# PULSECAPS.net
KiCad netlist of a schematic drawn in Altium Designer
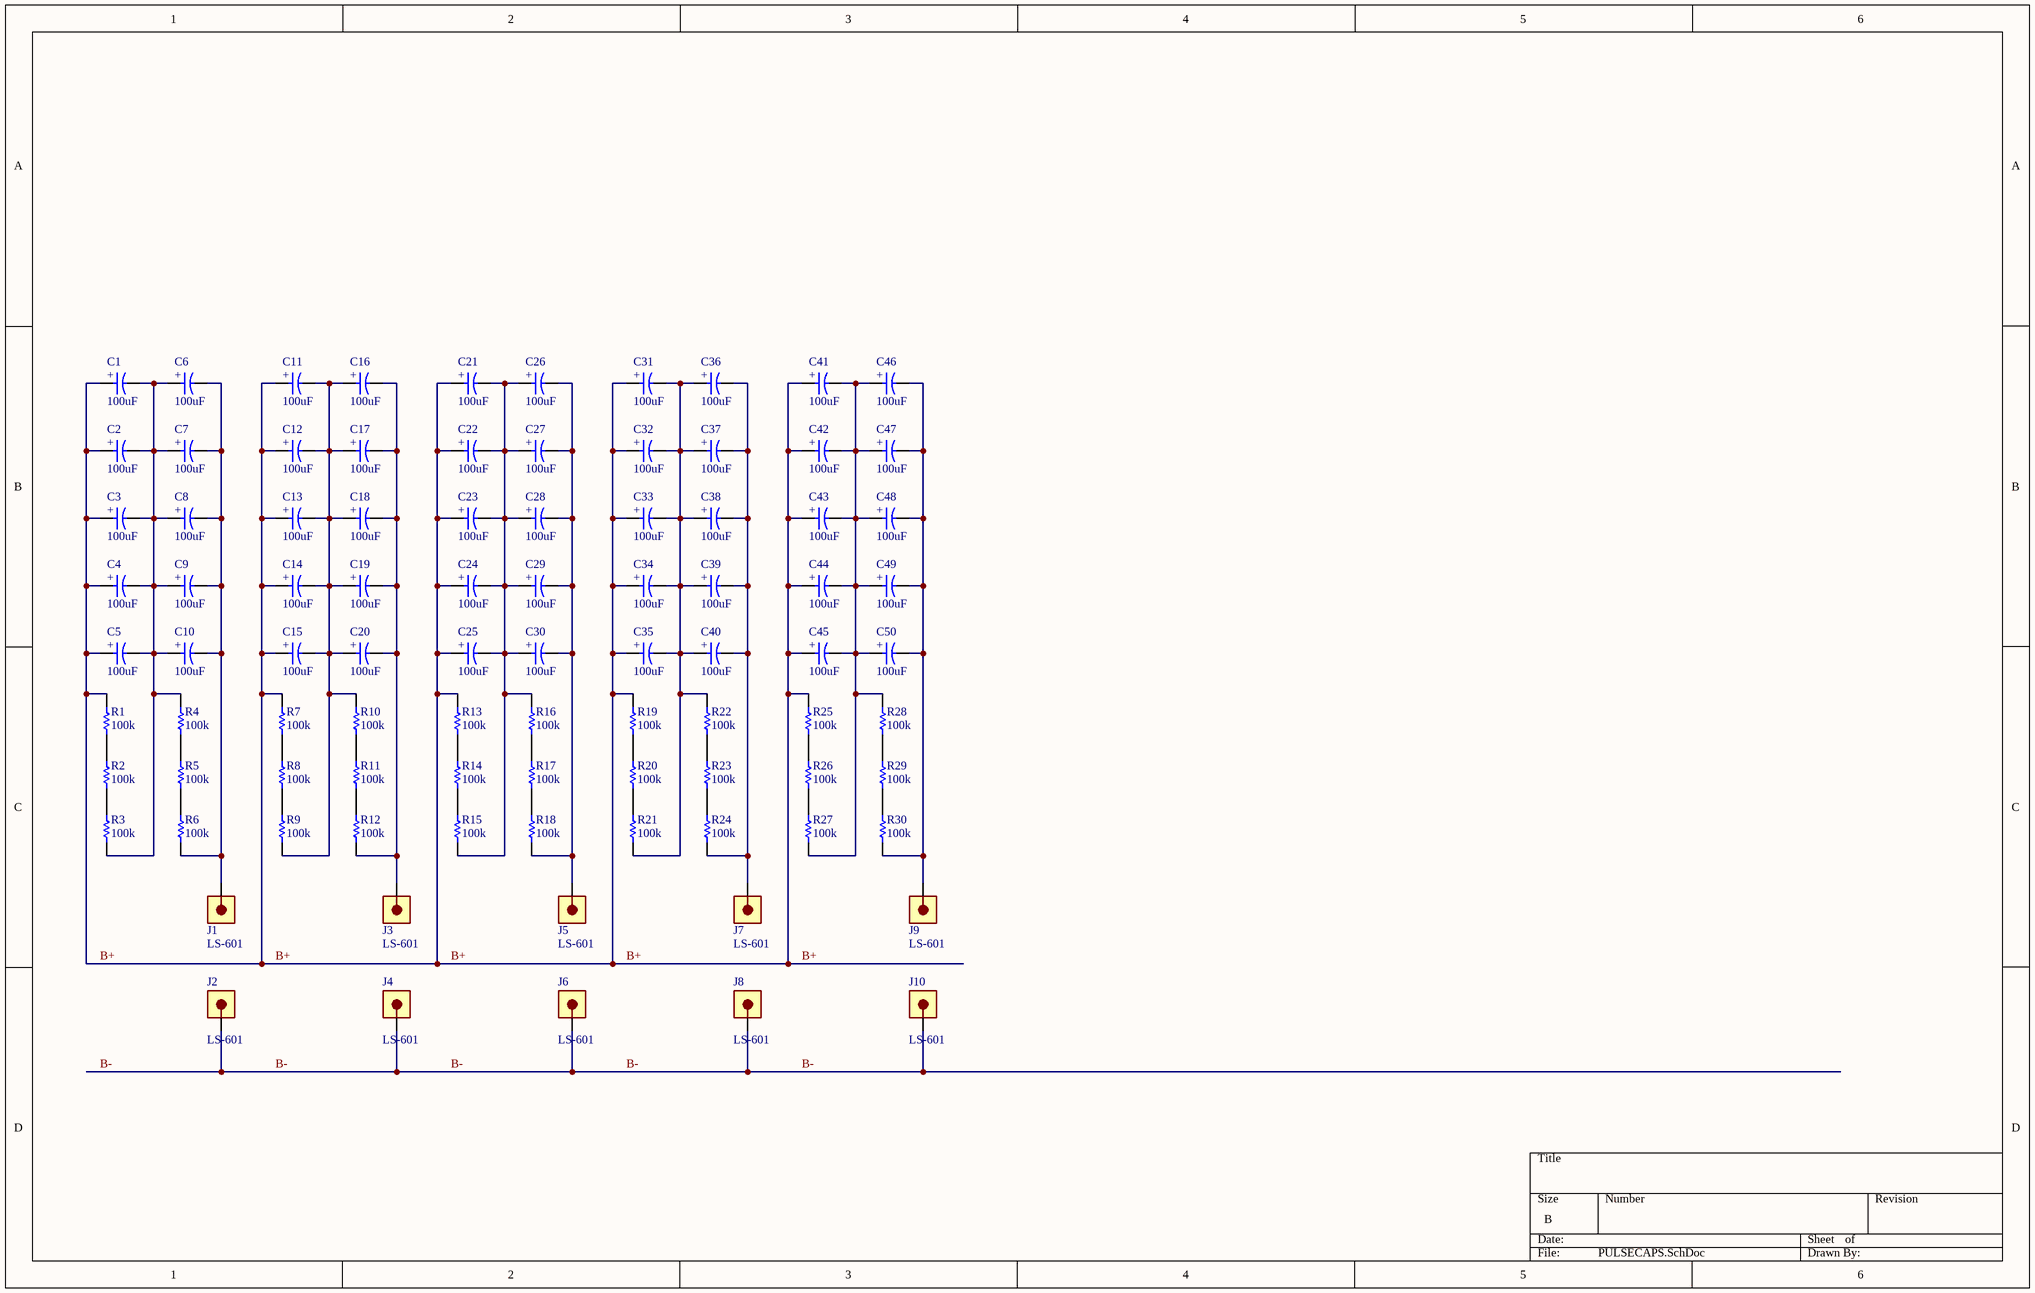
[diagram p0: PULSECAPS.SchDoc]

(export (version "E")
  (design (tool "Eeschema 10.0.6"))
  (components
    (comp (ref "C1")
      (value "100uF")
      (footprint "C_CAN_TH_7.5MM_LEADS")
      (description "C - CAPACITOR - ELECTROLYTIC - 100uF - 400V")
      (fields (field (name "LCSC PART #") "C441621") (field (name "Comment") "400BXW100MEFR16X30"))
      (libsource (lib "JLC_PCB") (part "400BXW100MEFR16X30"))
    )
    (comp (ref "C2")
      (value "100uF")
      (footprint "C_CAN_TH_7.5MM_LEADS")
      (description "C - CAPACITOR - ELECTROLYTIC - 100uF - 400V")
      (fields (field (name "LCSC PART #") "C441621") (field (name "Comment") "400BXW100MEFR16X30"))
      (libsource (lib "JLC_PCB") (part "400BXW100MEFR16X30"))
    )
    (comp (ref "C3")
      (value "100uF")
      (footprint "C_CAN_TH_7.5MM_LEADS")
      (description "C - CAPACITOR - ELECTROLYTIC - 100uF - 400V")
      (fields (field (name "LCSC PART #") "C441621") (field (name "Comment") "400BXW100MEFR16X30"))
      (libsource (lib "JLC_PCB") (part "400BXW100MEFR16X30"))
    )
    (comp (ref "C4")
      (value "100uF")
      (footprint "C_CAN_TH_7.5MM_LEADS")
      (description "C - CAPACITOR - ELECTROLYTIC - 100uF - 400V")
      (fields (field (name "LCSC PART #") "C441621") (field (name "Comment") "400BXW100MEFR16X30"))
      (libsource (lib "JLC_PCB") (part "400BXW100MEFR16X30"))
    )
    (comp (ref "C5")
      (value "100uF")
      (footprint "C_CAN_TH_7.5MM_LEADS")
      (description "C - CAPACITOR - ELECTROLYTIC - 100uF - 400V")
      (fields (field (name "LCSC PART #") "C441621") (field (name "Comment") "400BXW100MEFR16X30"))
      (libsource (lib "JLC_PCB") (part "400BXW100MEFR16X30"))
    )
    (comp (ref "C6")
      (value "100uF")
      (footprint "C_CAN_TH_7.5MM_LEADS")
      (description "C - CAPACITOR - ELECTROLYTIC - 100uF - 400V")
      (fields (field (name "LCSC PART #") "C441621") (field (name "Comment") "400BXW100MEFR16X30"))
      (libsource (lib "JLC_PCB") (part "400BXW100MEFR16X30"))
    )
    (comp (ref "C7")
      (value "100uF")
      (footprint "C_CAN_TH_7.5MM_LEADS")
      (description "C - CAPACITOR - ELECTROLYTIC - 100uF - 400V")
      (fields (field (name "LCSC PART #") "C441621") (field (name "Comment") "400BXW100MEFR16X30"))
      (libsource (lib "JLC_PCB") (part "400BXW100MEFR16X30"))
    )
    (comp (ref "C8")
      (value "100uF")
      (footprint "C_CAN_TH_7.5MM_LEADS")
      (description "C - CAPACITOR - ELECTROLYTIC - 100uF - 400V")
      (fields (field (name "LCSC PART #") "C441621") (field (name "Comment") "400BXW100MEFR16X30"))
      (libsource (lib "JLC_PCB") (part "400BXW100MEFR16X30"))
    )
    (comp (ref "C9")
      (value "100uF")
      (footprint "C_CAN_TH_7.5MM_LEADS")
      (description "C - CAPACITOR - ELECTROLYTIC - 100uF - 400V")
      (fields (field (name "LCSC PART #") "C441621") (field (name "Comment") "400BXW100MEFR16X30"))
      (libsource (lib "JLC_PCB") (part "400BXW100MEFR16X30"))
    )
    (comp (ref "C10")
      (value "100uF")
      (footprint "C_CAN_TH_7.5MM_LEADS")
      (description "C - CAPACITOR - ELECTROLYTIC - 100uF - 400V")
      (fields (field (name "LCSC PART #") "C441621") (field (name "Comment") "400BXW100MEFR16X30"))
      (libsource (lib "JLC_PCB") (part "400BXW100MEFR16X30"))
    )
    (comp (ref "C11")
      (value "100uF")
      (footprint "C_CAN_TH_7.5MM_LEADS")
      (description "C - CAPACITOR - ELECTROLYTIC - 100uF - 400V")
      (fields (field (name "LCSC PART #") "C441621") (field (name "Comment") "400BXW100MEFR16X30"))
      (libsource (lib "JLC_PCB") (part "400BXW100MEFR16X30"))
    )
    (comp (ref "C12")
      (value "100uF")
      (footprint "C_CAN_TH_7.5MM_LEADS")
      (description "C - CAPACITOR - ELECTROLYTIC - 100uF - 400V")
      (fields (field (name "LCSC PART #") "C441621") (field (name "Comment") "400BXW100MEFR16X30"))
      (libsource (lib "JLC_PCB") (part "400BXW100MEFR16X30"))
    )
    (comp (ref "C13")
      (value "100uF")
      (footprint "C_CAN_TH_7.5MM_LEADS")
      (description "C - CAPACITOR - ELECTROLYTIC - 100uF - 400V")
      (fields (field (name "LCSC PART #") "C441621") (field (name "Comment") "400BXW100MEFR16X30"))
      (libsource (lib "JLC_PCB") (part "400BXW100MEFR16X30"))
    )
    (comp (ref "C14")
      (value "100uF")
      (footprint "C_CAN_TH_7.5MM_LEADS")
      (description "C - CAPACITOR - ELECTROLYTIC - 100uF - 400V")
      (fields (field (name "LCSC PART #") "C441621") (field (name "Comment") "400BXW100MEFR16X30"))
      (libsource (lib "JLC_PCB") (part "400BXW100MEFR16X30"))
    )
    (comp (ref "C15")
      (value "100uF")
      (footprint "C_CAN_TH_7.5MM_LEADS")
      (description "C - CAPACITOR - ELECTROLYTIC - 100uF - 400V")
      (fields (field (name "LCSC PART #") "C441621") (field (name "Comment") "400BXW100MEFR16X30"))
      (libsource (lib "JLC_PCB") (part "400BXW100MEFR16X30"))
    )
    (comp (ref "C16")
      (value "100uF")
      (footprint "C_CAN_TH_7.5MM_LEADS")
      (description "C - CAPACITOR - ELECTROLYTIC - 100uF - 400V")
      (fields (field (name "LCSC PART #") "C441621") (field (name "Comment") "400BXW100MEFR16X30"))
      (libsource (lib "JLC_PCB") (part "400BXW100MEFR16X30"))
    )
    (comp (ref "C17")
      (value "100uF")
      (footprint "C_CAN_TH_7.5MM_LEADS")
      (description "C - CAPACITOR - ELECTROLYTIC - 100uF - 400V")
      (fields (field (name "LCSC PART #") "C441621") (field (name "Comment") "400BXW100MEFR16X30"))
      (libsource (lib "JLC_PCB") (part "400BXW100MEFR16X30"))
    )
    (comp (ref "C18")
      (value "100uF")
      (footprint "C_CAN_TH_7.5MM_LEADS")
      (description "C - CAPACITOR - ELECTROLYTIC - 100uF - 400V")
      (fields (field (name "LCSC PART #") "C441621") (field (name "Comment") "400BXW100MEFR16X30"))
      (libsource (lib "JLC_PCB") (part "400BXW100MEFR16X30"))
    )
    (comp (ref "C19")
      (value "100uF")
      (footprint "C_CAN_TH_7.5MM_LEADS")
      (description "C - CAPACITOR - ELECTROLYTIC - 100uF - 400V")
      (fields (field (name "LCSC PART #") "C441621") (field (name "Comment") "400BXW100MEFR16X30"))
      (libsource (lib "JLC_PCB") (part "400BXW100MEFR16X30"))
    )
    (comp (ref "C20")
      (value "100uF")
      (footprint "C_CAN_TH_7.5MM_LEADS")
      (description "C - CAPACITOR - ELECTROLYTIC - 100uF - 400V")
      (fields (field (name "LCSC PART #") "C441621") (field (name "Comment") "400BXW100MEFR16X30"))
      (libsource (lib "JLC_PCB") (part "400BXW100MEFR16X30"))
    )
    (comp (ref "C21")
      (value "100uF")
      (footprint "C_CAN_TH_7.5MM_LEADS")
      (description "C - CAPACITOR - ELECTROLYTIC - 100uF - 400V")
      (fields (field (name "LCSC PART #") "C441621") (field (name "Comment") "400BXW100MEFR16X30"))
      (libsource (lib "JLC_PCB") (part "400BXW100MEFR16X30"))
    )
    (comp (ref "C22")
      (value "100uF")
      (footprint "C_CAN_TH_7.5MM_LEADS")
      (description "C - CAPACITOR - ELECTROLYTIC - 100uF - 400V")
      (fields (field (name "LCSC PART #") "C441621") (field (name "Comment") "400BXW100MEFR16X30"))
      (libsource (lib "JLC_PCB") (part "400BXW100MEFR16X30"))
    )
    (comp (ref "C23")
      (value "100uF")
      (footprint "C_CAN_TH_7.5MM_LEADS")
      (description "C - CAPACITOR - ELECTROLYTIC - 100uF - 400V")
      (fields (field (name "LCSC PART #") "C441621") (field (name "Comment") "400BXW100MEFR16X30"))
      (libsource (lib "JLC_PCB") (part "400BXW100MEFR16X30"))
    )
    (comp (ref "C24")
      (value "100uF")
      (footprint "C_CAN_TH_7.5MM_LEADS")
      (description "C - CAPACITOR - ELECTROLYTIC - 100uF - 400V")
      (fields (field (name "LCSC PART #") "C441621") (field (name "Comment") "400BXW100MEFR16X30"))
      (libsource (lib "JLC_PCB") (part "400BXW100MEFR16X30"))
    )
    (comp (ref "C25")
      (value "100uF")
      (footprint "C_CAN_TH_7.5MM_LEADS")
      (description "C - CAPACITOR - ELECTROLYTIC - 100uF - 400V")
      (fields (field (name "LCSC PART #") "C441621") (field (name "Comment") "400BXW100MEFR16X30"))
      (libsource (lib "JLC_PCB") (part "400BXW100MEFR16X30"))
    )
    (comp (ref "C26")
      (value "100uF")
      (footprint "C_CAN_TH_7.5MM_LEADS")
      (description "C - CAPACITOR - ELECTROLYTIC - 100uF - 400V")
      (fields (field (name "LCSC PART #") "C441621") (field (name "Comment") "400BXW100MEFR16X30"))
      (libsource (lib "JLC_PCB") (part "400BXW100MEFR16X30"))
    )
    (comp (ref "C27")
      (value "100uF")
      (footprint "C_CAN_TH_7.5MM_LEADS")
      (description "C - CAPACITOR - ELECTROLYTIC - 100uF - 400V")
      (fields (field (name "LCSC PART #") "C441621") (field (name "Comment") "400BXW100MEFR16X30"))
      (libsource (lib "JLC_PCB") (part "400BXW100MEFR16X30"))
    )
    (comp (ref "C28")
      (value "100uF")
      (footprint "C_CAN_TH_7.5MM_LEADS")
      (description "C - CAPACITOR - ELECTROLYTIC - 100uF - 400V")
      (fields (field (name "LCSC PART #") "C441621") (field (name "Comment") "400BXW100MEFR16X30"))
      (libsource (lib "JLC_PCB") (part "400BXW100MEFR16X30"))
    )
    (comp (ref "C29")
      (value "100uF")
      (footprint "C_CAN_TH_7.5MM_LEADS")
      (description "C - CAPACITOR - ELECTROLYTIC - 100uF - 400V")
      (fields (field (name "LCSC PART #") "C441621") (field (name "Comment") "400BXW100MEFR16X30"))
      (libsource (lib "JLC_PCB") (part "400BXW100MEFR16X30"))
    )
    (comp (ref "C30")
      (value "100uF")
      (footprint "C_CAN_TH_7.5MM_LEADS")
      (description "C - CAPACITOR - ELECTROLYTIC - 100uF - 400V")
      (fields (field (name "LCSC PART #") "C441621") (field (name "Comment") "400BXW100MEFR16X30"))
      (libsource (lib "JLC_PCB") (part "400BXW100MEFR16X30"))
    )
    (comp (ref "C31")
      (value "100uF")
      (footprint "C_CAN_TH_7.5MM_LEADS")
      (description "C - CAPACITOR - ELECTROLYTIC - 100uF - 400V")
      (fields (field (name "LCSC PART #") "C441621") (field (name "Comment") "400BXW100MEFR16X30"))
      (libsource (lib "JLC_PCB") (part "400BXW100MEFR16X30"))
    )
    (comp (ref "C32")
      (value "100uF")
      (footprint "C_CAN_TH_7.5MM_LEADS")
      (description "C - CAPACITOR - ELECTROLYTIC - 100uF - 400V")
      (fields (field (name "LCSC PART #") "C441621") (field (name "Comment") "400BXW100MEFR16X30"))
      (libsource (lib "JLC_PCB") (part "400BXW100MEFR16X30"))
    )
    (comp (ref "C33")
      (value "100uF")
      (footprint "C_CAN_TH_7.5MM_LEADS")
      (description "C - CAPACITOR - ELECTROLYTIC - 100uF - 400V")
      (fields (field (name "LCSC PART #") "C441621") (field (name "Comment") "400BXW100MEFR16X30"))
      (libsource (lib "JLC_PCB") (part "400BXW100MEFR16X30"))
    )
    (comp (ref "C34")
      (value "100uF")
      (footprint "C_CAN_TH_7.5MM_LEADS")
      (description "C - CAPACITOR - ELECTROLYTIC - 100uF - 400V")
      (fields (field (name "LCSC PART #") "C441621") (field (name "Comment") "400BXW100MEFR16X30"))
      (libsource (lib "JLC_PCB") (part "400BXW100MEFR16X30"))
    )
    (comp (ref "C35")
      (value "100uF")
      (footprint "C_CAN_TH_7.5MM_LEADS")
      (description "C - CAPACITOR - ELECTROLYTIC - 100uF - 400V")
      (fields (field (name "LCSC PART #") "C441621") (field (name "Comment") "400BXW100MEFR16X30"))
      (libsource (lib "JLC_PCB") (part "400BXW100MEFR16X30"))
    )
    (comp (ref "C36")
      (value "100uF")
      (footprint "C_CAN_TH_7.5MM_LEADS")
      (description "C - CAPACITOR - ELECTROLYTIC - 100uF - 400V")
      (fields (field (name "LCSC PART #") "C441621") (field (name "Comment") "400BXW100MEFR16X30"))
      (libsource (lib "JLC_PCB") (part "400BXW100MEFR16X30"))
    )
    (comp (ref "C37")
      (value "100uF")
      (footprint "C_CAN_TH_7.5MM_LEADS")
      (description "C - CAPACITOR - ELECTROLYTIC - 100uF - 400V")
      (fields (field (name "LCSC PART #") "C441621") (field (name "Comment") "400BXW100MEFR16X30"))
      (libsource (lib "JLC_PCB") (part "400BXW100MEFR16X30"))
    )
    (comp (ref "C38")
      (value "100uF")
      (footprint "C_CAN_TH_7.5MM_LEADS")
      (description "C - CAPACITOR - ELECTROLYTIC - 100uF - 400V")
      (fields (field (name "LCSC PART #") "C441621") (field (name "Comment") "400BXW100MEFR16X30"))
      (libsource (lib "JLC_PCB") (part "400BXW100MEFR16X30"))
    )
    (comp (ref "C39")
      (value "100uF")
      (footprint "C_CAN_TH_7.5MM_LEADS")
      (description "C - CAPACITOR - ELECTROLYTIC - 100uF - 400V")
      (fields (field (name "LCSC PART #") "C441621") (field (name "Comment") "400BXW100MEFR16X30"))
      (libsource (lib "JLC_PCB") (part "400BXW100MEFR16X30"))
    )
    (comp (ref "C40")
      (value "100uF")
      (footprint "C_CAN_TH_7.5MM_LEADS")
      (description "C - CAPACITOR - ELECTROLYTIC - 100uF - 400V")
      (fields (field (name "LCSC PART #") "C441621") (field (name "Comment") "400BXW100MEFR16X30"))
      (libsource (lib "JLC_PCB") (part "400BXW100MEFR16X30"))
    )
    (comp (ref "C41")
      (value "100uF")
      (footprint "C_CAN_TH_7.5MM_LEADS")
      (description "C - CAPACITOR - ELECTROLYTIC - 100uF - 400V")
      (fields (field (name "LCSC PART #") "C441621") (field (name "Comment") "400BXW100MEFR16X30"))
      (libsource (lib "JLC_PCB") (part "400BXW100MEFR16X30"))
    )
    (comp (ref "C42")
      (value "100uF")
      (footprint "C_CAN_TH_7.5MM_LEADS")
      (description "C - CAPACITOR - ELECTROLYTIC - 100uF - 400V")
      (fields (field (name "LCSC PART #") "C441621") (field (name "Comment") "400BXW100MEFR16X30"))
      (libsource (lib "JLC_PCB") (part "400BXW100MEFR16X30"))
    )
    (comp (ref "C43")
      (value "100uF")
      (footprint "C_CAN_TH_7.5MM_LEADS")
      (description "C - CAPACITOR - ELECTROLYTIC - 100uF - 400V")
      (fields (field (name "LCSC PART #") "C441621") (field (name "Comment") "400BXW100MEFR16X30"))
      (libsource (lib "JLC_PCB") (part "400BXW100MEFR16X30"))
    )
    (comp (ref "C44")
      (value "100uF")
      (footprint "C_CAN_TH_7.5MM_LEADS")
      (description "C - CAPACITOR - ELECTROLYTIC - 100uF - 400V")
      (fields (field (name "LCSC PART #") "C441621") (field (name "Comment") "400BXW100MEFR16X30"))
      (libsource (lib "JLC_PCB") (part "400BXW100MEFR16X30"))
    )
    (comp (ref "C45")
      (value "100uF")
      (footprint "C_CAN_TH_7.5MM_LEADS")
      (description "C - CAPACITOR - ELECTROLYTIC - 100uF - 400V")
      (fields (field (name "LCSC PART #") "C441621") (field (name "Comment") "400BXW100MEFR16X30"))
      (libsource (lib "JLC_PCB") (part "400BXW100MEFR16X30"))
    )
    (comp (ref "C46")
      (value "100uF")
      (footprint "C_CAN_TH_7.5MM_LEADS")
      (description "C - CAPACITOR - ELECTROLYTIC - 100uF - 400V")
      (fields (field (name "LCSC PART #") "C441621") (field (name "Comment") "400BXW100MEFR16X30"))
      (libsource (lib "JLC_PCB") (part "400BXW100MEFR16X30"))
    )
    (comp (ref "C47")
      (value "100uF")
      (footprint "C_CAN_TH_7.5MM_LEADS")
      (description "C - CAPACITOR - ELECTROLYTIC - 100uF - 400V")
      (fields (field (name "LCSC PART #") "C441621") (field (name "Comment") "400BXW100MEFR16X30"))
      (libsource (lib "JLC_PCB") (part "400BXW100MEFR16X30"))
    )
    (comp (ref "C48")
      (value "100uF")
      (footprint "C_CAN_TH_7.5MM_LEADS")
      (description "C - CAPACITOR - ELECTROLYTIC - 100uF - 400V")
      (fields (field (name "LCSC PART #") "C441621") (field (name "Comment") "400BXW100MEFR16X30"))
      (libsource (lib "JLC_PCB") (part "400BXW100MEFR16X30"))
    )
    (comp (ref "C49")
      (value "100uF")
      (footprint "C_CAN_TH_7.5MM_LEADS")
      (description "C - CAPACITOR - ELECTROLYTIC - 100uF - 400V")
      (fields (field (name "LCSC PART #") "C441621") (field (name "Comment") "400BXW100MEFR16X30"))
      (libsource (lib "JLC_PCB") (part "400BXW100MEFR16X30"))
    )
    (comp (ref "C50")
      (value "100uF")
      (footprint "C_CAN_TH_7.5MM_LEADS")
      (description "C - CAPACITOR - ELECTROLYTIC - 100uF - 400V")
      (fields (field (name "LCSC PART #") "C441621") (field (name "Comment") "400BXW100MEFR16X30"))
      (libsource (lib "JLC_PCB") (part "400BXW100MEFR16X30"))
    )
    (comp (ref "J1")
      (value "LS-601")
      (footprint "LS-601")
      (description "J - JACK - FUSEHOLDER - 6X30 - THT")
      (fields (field (name "LCSC PART #") "C182321"))
      (libsource (lib "JLC_PCB") (part "LS-601"))
    )
    (comp (ref "J2")
      (value "LS-601")
      (footprint "LS-601")
      (description "J - JACK - FUSEHOLDER - 6X30 - THT")
      (fields (field (name "LCSC PART #") "C182321"))
      (libsource (lib "") (part "LS-601_1"))
    )
    (comp (ref "J3")
      (value "LS-601")
      (footprint "LS-601")
      (description "J - JACK - FUSEHOLDER - 6X30 - THT")
      (fields (field (name "LCSC PART #") "C182321"))
      (libsource (lib "JLC_PCB") (part "LS-601"))
    )
    (comp (ref "J4")
      (value "LS-601")
      (footprint "LS-601")
      (description "J - JACK - FUSEHOLDER - 6X30 - THT")
      (fields (field (name "LCSC PART #") "C182321"))
      (libsource (lib "") (part "LS-601_1"))
    )
    (comp (ref "J5")
      (value "LS-601")
      (footprint "LS-601")
      (description "J - JACK - FUSEHOLDER - 6X30 - THT")
      (fields (field (name "LCSC PART #") "C182321"))
      (libsource (lib "JLC_PCB") (part "LS-601"))
    )
    (comp (ref "J6")
      (value "LS-601")
      (footprint "LS-601")
      (description "J - JACK - FUSEHOLDER - 6X30 - THT")
      (fields (field (name "LCSC PART #") "C182321"))
      (libsource (lib "") (part "LS-601_1"))
    )
    (comp (ref "J7")
      (value "LS-601")
      (footprint "LS-601")
      (description "J - JACK - FUSEHOLDER - 6X30 - THT")
      (fields (field (name "LCSC PART #") "C182321"))
      (libsource (lib "JLC_PCB") (part "LS-601"))
    )
    (comp (ref "J8")
      (value "LS-601")
      (footprint "LS-601")
      (description "J - JACK - FUSEHOLDER - 6X30 - THT")
      (fields (field (name "LCSC PART #") "C182321"))
      (libsource (lib "") (part "LS-601_1"))
    )
    (comp (ref "J9")
      (value "LS-601")
      (footprint "LS-601")
      (description "J - JACK - FUSEHOLDER - 6X30 - THT")
      (fields (field (name "LCSC PART #") "C182321"))
      (libsource (lib "JLC_PCB") (part "LS-601"))
    )
    (comp (ref "J10")
      (value "LS-601")
      (footprint "LS-601")
      (description "J - JACK - FUSEHOLDER - 6X30 - THT")
      (fields (field (name "LCSC PART #") "C182321"))
      (libsource (lib "") (part "LS-601_1"))
    )
    (comp (ref "R1")
      (value "100k")
      (footprint "R_1206")
      (description "R - RESISTOR - SMD - 100k - 1% - 1206")
      (fields (field (name "LCSC PART #") "C17900") (field (name "Comment") "1206W4F1003T5E"))
      (libsource (lib "JLC_PCB") (part "1206W4F1003T5E"))
    )
    (comp (ref "R2")
      (value "100k")
      (footprint "R_1206")
      (description "R - RESISTOR - SMD - 100k - 1% - 1206")
      (fields (field (name "LCSC PART #") "C17900") (field (name "Comment") "1206W4F1003T5E"))
      (libsource (lib "JLC_PCB") (part "1206W4F1003T5E"))
    )
    (comp (ref "R3")
      (value "100k")
      (footprint "R_1206")
      (description "R - RESISTOR - SMD - 100k - 1% - 1206")
      (fields (field (name "LCSC PART #") "C17900") (field (name "Comment") "1206W4F1003T5E"))
      (libsource (lib "JLC_PCB") (part "1206W4F1003T5E"))
    )
    (comp (ref "R4")
      (value "100k")
      (footprint "R_1206")
      (description "R - RESISTOR - SMD - 100k - 1% - 1206")
      (fields (field (name "LCSC PART #") "C17900") (field (name "Comment") "1206W4F1003T5E"))
      (libsource (lib "JLC_PCB") (part "1206W4F1003T5E"))
    )
    (comp (ref "R5")
      (value "100k")
      (footprint "R_1206")
      (description "R - RESISTOR - SMD - 100k - 1% - 1206")
      (fields (field (name "LCSC PART #") "C17900") (field (name "Comment") "1206W4F1003T5E"))
      (libsource (lib "JLC_PCB") (part "1206W4F1003T5E"))
    )
    (comp (ref "R6")
      (value "100k")
      (footprint "R_1206")
      (description "R - RESISTOR - SMD - 100k - 1% - 1206")
      (fields (field (name "LCSC PART #") "C17900") (field (name "Comment") "1206W4F1003T5E"))
      (libsource (lib "JLC_PCB") (part "1206W4F1003T5E"))
    )
    (comp (ref "R7")
      (value "100k")
      (footprint "R_1206")
      (description "R - RESISTOR - SMD - 100k - 1% - 1206")
      (fields (field (name "LCSC PART #") "C17900") (field (name "Comment") "1206W4F1003T5E"))
      (libsource (lib "JLC_PCB") (part "1206W4F1003T5E"))
    )
    (comp (ref "R8")
      (value "100k")
      (footprint "R_1206")
      (description "R - RESISTOR - SMD - 100k - 1% - 1206")
      (fields (field (name "LCSC PART #") "C17900") (field (name "Comment") "1206W4F1003T5E"))
      (libsource (lib "JLC_PCB") (part "1206W4F1003T5E"))
    )
    (comp (ref "R9")
      (value "100k")
      (footprint "R_1206")
      (description "R - RESISTOR - SMD - 100k - 1% - 1206")
      (fields (field (name "LCSC PART #") "C17900") (field (name "Comment") "1206W4F1003T5E"))
      (libsource (lib "JLC_PCB") (part "1206W4F1003T5E"))
    )
    (comp (ref "R10")
      (value "100k")
      (footprint "R_1206")
      (description "R - RESISTOR - SMD - 100k - 1% - 1206")
      (fields (field (name "LCSC PART #") "C17900") (field (name "Comment") "1206W4F1003T5E"))
      (libsource (lib "JLC_PCB") (part "1206W4F1003T5E"))
    )
    (comp (ref "R11")
      (value "100k")
      (footprint "R_1206")
      (description "R - RESISTOR - SMD - 100k - 1% - 1206")
      (fields (field (name "LCSC PART #") "C17900") (field (name "Comment") "1206W4F1003T5E"))
      (libsource (lib "JLC_PCB") (part "1206W4F1003T5E"))
    )
    (comp (ref "R12")
      (value "100k")
      (footprint "R_1206")
      (description "R - RESISTOR - SMD - 100k - 1% - 1206")
      (fields (field (name "LCSC PART #") "C17900") (field (name "Comment") "1206W4F1003T5E"))
      (libsource (lib "JLC_PCB") (part "1206W4F1003T5E"))
    )
    (comp (ref "R13")
      (value "100k")
      (footprint "R_1206")
      (description "R - RESISTOR - SMD - 100k - 1% - 1206")
      (fields (field (name "LCSC PART #") "C17900") (field (name "Comment") "1206W4F1003T5E"))
      (libsource (lib "JLC_PCB") (part "1206W4F1003T5E"))
    )
    (comp (ref "R14")
      (value "100k")
      (footprint "R_1206")
      (description "R - RESISTOR - SMD - 100k - 1% - 1206")
      (fields (field (name "LCSC PART #") "C17900") (field (name "Comment") "1206W4F1003T5E"))
      (libsource (lib "JLC_PCB") (part "1206W4F1003T5E"))
    )
    (comp (ref "R15")
      (value "100k")
      (footprint "R_1206")
      (description "R - RESISTOR - SMD - 100k - 1% - 1206")
      (fields (field (name "LCSC PART #") "C17900") (field (name "Comment") "1206W4F1003T5E"))
      (libsource (lib "JLC_PCB") (part "1206W4F1003T5E"))
    )
    (comp (ref "R16")
      (value "100k")
      (footprint "R_1206")
      (description "R - RESISTOR - SMD - 100k - 1% - 1206")
      (fields (field (name "LCSC PART #") "C17900") (field (name "Comment") "1206W4F1003T5E"))
      (libsource (lib "JLC_PCB") (part "1206W4F1003T5E"))
    )
    (comp (ref "R17")
      (value "100k")
      (footprint "R_1206")
      (description "R - RESISTOR - SMD - 100k - 1% - 1206")
      (fields (field (name "LCSC PART #") "C17900") (field (name "Comment") "1206W4F1003T5E"))
      (libsource (lib "JLC_PCB") (part "1206W4F1003T5E"))
    )
    (comp (ref "R18")
      (value "100k")
      (footprint "R_1206")
      (description "R - RESISTOR - SMD - 100k - 1% - 1206")
      (fields (field (name "LCSC PART #") "C17900") (field (name "Comment") "1206W4F1003T5E"))
      (libsource (lib "JLC_PCB") (part "1206W4F1003T5E"))
    )
    (comp (ref "R19")
      (value "100k")
      (footprint "R_1206")
      (description "R - RESISTOR - SMD - 100k - 1% - 1206")
      (fields (field (name "LCSC PART #") "C17900") (field (name "Comment") "1206W4F1003T5E"))
      (libsource (lib "JLC_PCB") (part "1206W4F1003T5E"))
    )
    (comp (ref "R20")
      (value "100k")
      (footprint "R_1206")
      (description "R - RESISTOR - SMD - 100k - 1% - 1206")
      (fields (field (name "LCSC PART #") "C17900") (field (name "Comment") "1206W4F1003T5E"))
      (libsource (lib "JLC_PCB") (part "1206W4F1003T5E"))
    )
    (comp (ref "R21")
      (value "100k")
      (footprint "R_1206")
      (description "R - RESISTOR - SMD - 100k - 1% - 1206")
      (fields (field (name "LCSC PART #") "C17900") (field (name "Comment") "1206W4F1003T5E"))
      (libsource (lib "JLC_PCB") (part "1206W4F1003T5E"))
    )
    (comp (ref "R22")
      (value "100k")
      (footprint "R_1206")
      (description "R - RESISTOR - SMD - 100k - 1% - 1206")
      (fields (field (name "LCSC PART #") "C17900") (field (name "Comment") "1206W4F1003T5E"))
      (libsource (lib "JLC_PCB") (part "1206W4F1003T5E"))
    )
    (comp (ref "R23")
      (value "100k")
      (footprint "R_1206")
      (description "R - RESISTOR - SMD - 100k - 1% - 1206")
      (fields (field (name "LCSC PART #") "C17900") (field (name "Comment") "1206W4F1003T5E"))
      (libsource (lib "JLC_PCB") (part "1206W4F1003T5E"))
    )
    (comp (ref "R24")
      (value "100k")
      (footprint "R_1206")
      (description "R - RESISTOR - SMD - 100k - 1% - 1206")
      (fields (field (name "LCSC PART #") "C17900") (field (name "Comment") "1206W4F1003T5E"))
      (libsource (lib "JLC_PCB") (part "1206W4F1003T5E"))
    )
    (comp (ref "R25")
      (value "100k")
      (footprint "R_1206")
      (description "R - RESISTOR - SMD - 100k - 1% - 1206")
      (fields (field (name "LCSC PART #") "C17900") (field (name "Comment") "1206W4F1003T5E"))
      (libsource (lib "JLC_PCB") (part "1206W4F1003T5E"))
    )
    (comp (ref "R26")
      (value "100k")
      (footprint "R_1206")
      (description "R - RESISTOR - SMD - 100k - 1% - 1206")
      (fields (field (name "LCSC PART #") "C17900") (field (name "Comment") "1206W4F1003T5E"))
      (libsource (lib "JLC_PCB") (part "1206W4F1003T5E"))
    )
    (comp (ref "R27")
      (value "100k")
      (footprint "R_1206")
      (description "R - RESISTOR - SMD - 100k - 1% - 1206")
      (fields (field (name "LCSC PART #") "C17900") (field (name "Comment") "1206W4F1003T5E"))
      (libsource (lib "JLC_PCB") (part "1206W4F1003T5E"))
    )
    (comp (ref "R28")
      (value "100k")
      (footprint "R_1206")
      (description "R - RESISTOR - SMD - 100k - 1% - 1206")
      (fields (field (name "LCSC PART #") "C17900") (field (name "Comment") "1206W4F1003T5E"))
      (libsource (lib "JLC_PCB") (part "1206W4F1003T5E"))
    )
    (comp (ref "R29")
      (value "100k")
      (footprint "R_1206")
      (description "R - RESISTOR - SMD - 100k - 1% - 1206")
      (fields (field (name "LCSC PART #") "C17900") (field (name "Comment") "1206W4F1003T5E"))
      (libsource (lib "JLC_PCB") (part "1206W4F1003T5E"))
    )
    (comp (ref "R30")
      (value "100k")
      (footprint "R_1206")
      (description "R - RESISTOR - SMD - 100k - 1% - 1206")
      (fields (field (name "LCSC PART #") "C17900") (field (name "Comment") "1206W4F1003T5E"))
      (libsource (lib "JLC_PCB") (part "1206W4F1003T5E"))
    )
  )
  (nets
    (net (code "1") (name "/B+") (class "Default")
      (node (ref "C1") (pin "2") (pinfunction "2_2") (pintype "passive"))
      (node (ref "C11") (pin "2") (pinfunction "2_2") (pintype "passive"))
      (node (ref "C12") (pin "2") (pinfunction "2_2") (pintype "passive"))
      (node (ref "C13") (pin "2") (pinfunction "2_2") (pintype "passive"))
      (node (ref "C14") (pin "2") (pinfunction "2_2") (pintype "passive"))
      (node (ref "C15") (pin "2") (pinfunction "2_2") (pintype "passive"))
      (node (ref "C2") (pin "2") (pinfunction "2_2") (pintype "passive"))
      (node (ref "C21") (pin "2") (pinfunction "2_2") (pintype "passive"))
      (node (ref "C22") (pin "2") (pinfunction "2_2") (pintype "passive"))
      (node (ref "C23") (pin "2") (pinfunction "2_2") (pintype "passive"))
      (node (ref "C24") (pin "2") (pinfunction "2_2") (pintype "passive"))
      (node (ref "C25") (pin "2") (pinfunction "2_2") (pintype "passive"))
      (node (ref "C3") (pin "2") (pinfunction "2_2") (pintype "passive"))
      (node (ref "C31") (pin "2") (pinfunction "2_2") (pintype "passive"))
      (node (ref "C32") (pin "2") (pinfunction "2_2") (pintype "passive"))
      (node (ref "C33") (pin "2") (pinfunction "2_2") (pintype "passive"))
      (node (ref "C34") (pin "2") (pinfunction "2_2") (pintype "passive"))
      (node (ref "C35") (pin "2") (pinfunction "2_2") (pintype "passive"))
      (node (ref "C4") (pin "2") (pinfunction "2_2") (pintype "passive"))
      (node (ref "C41") (pin "2") (pinfunction "2_2") (pintype "passive"))
      (node (ref "C42") (pin "2") (pinfunction "2_2") (pintype "passive"))
      (node (ref "C43") (pin "2") (pinfunction "2_2") (pintype "passive"))
      (node (ref "C44") (pin "2") (pinfunction "2_2") (pintype "passive"))
      (node (ref "C45") (pin "2") (pinfunction "2_2") (pintype "passive"))
      (node (ref "C5") (pin "2") (pinfunction "2_2") (pintype "passive"))
      (node (ref "R1") (pin "2") (pinfunction "2_2") (pintype "passive"))
      (node (ref "R13") (pin "2") (pinfunction "2_2") (pintype "passive"))
      (node (ref "R19") (pin "2") (pinfunction "2_2") (pintype "passive"))
      (node (ref "R25") (pin "2") (pinfunction "2_2") (pintype "passive"))
      (node (ref "R7") (pin "2") (pinfunction "2_2") (pintype "passive"))
    )
    (net (code "2") (name "/B-") (class "Default")
      (node (ref "J10") (pin "1") (pinfunction "1_1") (pintype "passive"))
      (node (ref "J2") (pin "1") (pinfunction "1_1") (pintype "passive"))
      (node (ref "J4") (pin "1") (pinfunction "1_1") (pintype "passive"))
      (node (ref "J6") (pin "1") (pinfunction "1_1") (pintype "passive"))
      (node (ref "J8") (pin "1") (pinfunction "1_1") (pintype "passive"))
    )
    (net (code "3") (name "Net-(C1-Pad1)") (class "Default")
      (node (ref "C1") (pin "1") (pinfunction "1_1") (pintype "passive"))
      (node (ref "C10") (pin "2") (pinfunction "2_2") (pintype "passive"))
      (node (ref "C2") (pin "1") (pinfunction "1_1") (pintype "passive"))
      (node (ref "C3") (pin "1") (pinfunction "1_1") (pintype "passive"))
      (node (ref "C4") (pin "1") (pinfunction "1_1") (pintype "passive"))
      (node (ref "C5") (pin "1") (pinfunction "1_1") (pintype "passive"))
      (node (ref "C6") (pin "2") (pinfunction "2_2") (pintype "passive"))
      (node (ref "C7") (pin "2") (pinfunction "2_2") (pintype "passive"))
      (node (ref "C8") (pin "2") (pinfunction "2_2") (pintype "passive"))
      (node (ref "C9") (pin "2") (pinfunction "2_2") (pintype "passive"))
      (node (ref "R3") (pin "1") (pinfunction "1_1") (pintype "passive"))
      (node (ref "R4") (pin "2") (pinfunction "2_2") (pintype "passive"))
    )
    (net (code "4") (name "Net-(C10-Pad1)") (class "Default")
      (node (ref "C10") (pin "1") (pinfunction "1_1") (pintype "passive"))
      (node (ref "C6") (pin "1") (pinfunction "1_1") (pintype "passive"))
      (node (ref "C7") (pin "1") (pinfunction "1_1") (pintype "passive"))
      (node (ref "C8") (pin "1") (pinfunction "1_1") (pintype "passive"))
      (node (ref "C9") (pin "1") (pinfunction "1_1") (pintype "passive"))
      (node (ref "J1") (pin "1") (pinfunction "1_1") (pintype "passive"))
      (node (ref "R6") (pin "1") (pinfunction "1_1") (pintype "passive"))
    )
    (net (code "5") (name "Net-(C11-Pad1)") (class "Default")
      (node (ref "C11") (pin "1") (pinfunction "1_1") (pintype "passive"))
      (node (ref "C12") (pin "1") (pinfunction "1_1") (pintype "passive"))
      (node (ref "C13") (pin "1") (pinfunction "1_1") (pintype "passive"))
      (node (ref "C14") (pin "1") (pinfunction "1_1") (pintype "passive"))
      (node (ref "C15") (pin "1") (pinfunction "1_1") (pintype "passive"))
      (node (ref "C16") (pin "2") (pinfunction "2_2") (pintype "passive"))
      (node (ref "C17") (pin "2") (pinfunction "2_2") (pintype "passive"))
      (node (ref "C18") (pin "2") (pinfunction "2_2") (pintype "passive"))
      (node (ref "C19") (pin "2") (pinfunction "2_2") (pintype "passive"))
      (node (ref "C20") (pin "2") (pinfunction "2_2") (pintype "passive"))
      (node (ref "R10") (pin "2") (pinfunction "2_2") (pintype "passive"))
      (node (ref "R9") (pin "1") (pinfunction "1_1") (pintype "passive"))
    )
    (net (code "6") (name "Net-(C16-Pad1)") (class "Default")
      (node (ref "C16") (pin "1") (pinfunction "1_1") (pintype "passive"))
      (node (ref "C17") (pin "1") (pinfunction "1_1") (pintype "passive"))
      (node (ref "C18") (pin "1") (pinfunction "1_1") (pintype "passive"))
      (node (ref "C19") (pin "1") (pinfunction "1_1") (pintype "passive"))
      (node (ref "C20") (pin "1") (pinfunction "1_1") (pintype "passive"))
      (node (ref "J3") (pin "1") (pinfunction "1_1") (pintype "passive"))
      (node (ref "R12") (pin "1") (pinfunction "1_1") (pintype "passive"))
    )
    (net (code "7") (name "Net-(C21-Pad1)") (class "Default")
      (node (ref "C21") (pin "1") (pinfunction "1_1") (pintype "passive"))
      (node (ref "C22") (pin "1") (pinfunction "1_1") (pintype "passive"))
      (node (ref "C23") (pin "1") (pinfunction "1_1") (pintype "passive"))
      (node (ref "C24") (pin "1") (pinfunction "1_1") (pintype "passive"))
      (node (ref "C25") (pin "1") (pinfunction "1_1") (pintype "passive"))
      (node (ref "C26") (pin "2") (pinfunction "2_2") (pintype "passive"))
      (node (ref "C27") (pin "2") (pinfunction "2_2") (pintype "passive"))
      (node (ref "C28") (pin "2") (pinfunction "2_2") (pintype "passive"))
      (node (ref "C29") (pin "2") (pinfunction "2_2") (pintype "passive"))
      (node (ref "C30") (pin "2") (pinfunction "2_2") (pintype "passive"))
      (node (ref "R15") (pin "1") (pinfunction "1_1") (pintype "passive"))
      (node (ref "R16") (pin "2") (pinfunction "2_2") (pintype "passive"))
    )
    (net (code "8") (name "Net-(C26-Pad1)") (class "Default")
      (node (ref "C26") (pin "1") (pinfunction "1_1") (pintype "passive"))
      (node (ref "C27") (pin "1") (pinfunction "1_1") (pintype "passive"))
      (node (ref "C28") (pin "1") (pinfunction "1_1") (pintype "passive"))
      (node (ref "C29") (pin "1") (pinfunction "1_1") (pintype "passive"))
      (node (ref "C30") (pin "1") (pinfunction "1_1") (pintype "passive"))
      (node (ref "J5") (pin "1") (pinfunction "1_1") (pintype "passive"))
      (node (ref "R18") (pin "1") (pinfunction "1_1") (pintype "passive"))
    )
    (net (code "9") (name "Net-(C31-Pad1)") (class "Default")
      (node (ref "C31") (pin "1") (pinfunction "1_1") (pintype "passive"))
      (node (ref "C32") (pin "1") (pinfunction "1_1") (pintype "passive"))
      (node (ref "C33") (pin "1") (pinfunction "1_1") (pintype "passive"))
      (node (ref "C34") (pin "1") (pinfunction "1_1") (pintype "passive"))
      (node (ref "C35") (pin "1") (pinfunction "1_1") (pintype "passive"))
      (node (ref "C36") (pin "2") (pinfunction "2_2") (pintype "passive"))
      (node (ref "C37") (pin "2") (pinfunction "2_2") (pintype "passive"))
      (node (ref "C38") (pin "2") (pinfunction "2_2") (pintype "passive"))
      (node (ref "C39") (pin "2") (pinfunction "2_2") (pintype "passive"))
      (node (ref "C40") (pin "2") (pinfunction "2_2") (pintype "passive"))
      (node (ref "R21") (pin "1") (pinfunction "1_1") (pintype "passive"))
      (node (ref "R22") (pin "2") (pinfunction "2_2") (pintype "passive"))
    )
    (net (code "10") (name "Net-(C36-Pad1)") (class "Default")
      (node (ref "C36") (pin "1") (pinfunction "1_1") (pintype "passive"))
      (node (ref "C37") (pin "1") (pinfunction "1_1") (pintype "passive"))
      (node (ref "C38") (pin "1") (pinfunction "1_1") (pintype "passive"))
      (node (ref "C39") (pin "1") (pinfunction "1_1") (pintype "passive"))
      (node (ref "C40") (pin "1") (pinfunction "1_1") (pintype "passive"))
      (node (ref "J7") (pin "1") (pinfunction "1_1") (pintype "passive"))
      (node (ref "R24") (pin "1") (pinfunction "1_1") (pintype "passive"))
    )
    (net (code "11") (name "Net-(C41-Pad1)") (class "Default")
      (node (ref "C41") (pin "1") (pinfunction "1_1") (pintype "passive"))
      (node (ref "C42") (pin "1") (pinfunction "1_1") (pintype "passive"))
      (node (ref "C43") (pin "1") (pinfunction "1_1") (pintype "passive"))
      (node (ref "C44") (pin "1") (pinfunction "1_1") (pintype "passive"))
      (node (ref "C45") (pin "1") (pinfunction "1_1") (pintype "passive"))
      (node (ref "C46") (pin "2") (pinfunction "2_2") (pintype "passive"))
      (node (ref "C47") (pin "2") (pinfunction "2_2") (pintype "passive"))
      (node (ref "C48") (pin "2") (pinfunction "2_2") (pintype "passive"))
      (node (ref "C49") (pin "2") (pinfunction "2_2") (pintype "passive"))
      (node (ref "C50") (pin "2") (pinfunction "2_2") (pintype "passive"))
      (node (ref "R27") (pin "1") (pinfunction "1_1") (pintype "passive"))
      (node (ref "R28") (pin "2") (pinfunction "2_2") (pintype "passive"))
    )
    (net (code "12") (name "Net-(C46-Pad1)") (class "Default")
      (node (ref "C46") (pin "1") (pinfunction "1_1") (pintype "passive"))
      (node (ref "C47") (pin "1") (pinfunction "1_1") (pintype "passive"))
      (node (ref "C48") (pin "1") (pinfunction "1_1") (pintype "passive"))
      (node (ref "C49") (pin "1") (pinfunction "1_1") (pintype "passive"))
      (node (ref "C50") (pin "1") (pinfunction "1_1") (pintype "passive"))
      (node (ref "J9") (pin "1") (pinfunction "1_1") (pintype "passive"))
      (node (ref "R30") (pin "1") (pinfunction "1_1") (pintype "passive"))
    )
    (net (code "13") (name "Net-(R1-Pad1)") (class "Default")
      (node (ref "R1") (pin "1") (pinfunction "1_1") (pintype "passive"))
      (node (ref "R2") (pin "2") (pinfunction "2_2") (pintype "passive"))
    )
    (net (code "14") (name "Net-(R2-Pad1)") (class "Default")
      (node (ref "R2") (pin "1") (pinfunction "1_1") (pintype "passive"))
      (node (ref "R3") (pin "2") (pinfunction "2_2") (pintype "passive"))
    )
    (net (code "15") (name "Net-(R4-Pad1)") (class "Default")
      (node (ref "R4") (pin "1") (pinfunction "1_1") (pintype "passive"))
      (node (ref "R5") (pin "2") (pinfunction "2_2") (pintype "passive"))
    )
    (net (code "16") (name "Net-(R5-Pad1)") (class "Default")
      (node (ref "R5") (pin "1") (pinfunction "1_1") (pintype "passive"))
      (node (ref "R6") (pin "2") (pinfunction "2_2") (pintype "passive"))
    )
    (net (code "17") (name "Net-(R7-Pad1)") (class "Default")
      (node (ref "R7") (pin "1") (pinfunction "1_1") (pintype "passive"))
      (node (ref "R8") (pin "2") (pinfunction "2_2") (pintype "passive"))
    )
    (net (code "18") (name "Net-(R8-Pad1)") (class "Default")
      (node (ref "R8") (pin "1") (pinfunction "1_1") (pintype "passive"))
      (node (ref "R9") (pin "2") (pinfunction "2_2") (pintype "passive"))
    )
    (net (code "19") (name "Net-(R10-Pad1)") (class "Default")
      (node (ref "R10") (pin "1") (pinfunction "1_1") (pintype "passive"))
      (node (ref "R11") (pin "2") (pinfunction "2_2") (pintype "passive"))
    )
    (net (code "20") (name "Net-(R11-Pad1)") (class "Default")
      (node (ref "R11") (pin "1") (pinfunction "1_1") (pintype "passive"))
      (node (ref "R12") (pin "2") (pinfunction "2_2") (pintype "passive"))
    )
    (net (code "21") (name "Net-(R13-Pad1)") (class "Default")
      (node (ref "R13") (pin "1") (pinfunction "1_1") (pintype "passive"))
      (node (ref "R14") (pin "2") (pinfunction "2_2") (pintype "passive"))
    )
    (net (code "22") (name "Net-(R14-Pad1)") (class "Default")
      (node (ref "R14") (pin "1") (pinfunction "1_1") (pintype "passive"))
      (node (ref "R15") (pin "2") (pinfunction "2_2") (pintype "passive"))
    )
    (net (code "23") (name "Net-(R16-Pad1)") (class "Default")
      (node (ref "R16") (pin "1") (pinfunction "1_1") (pintype "passive"))
      (node (ref "R17") (pin "2") (pinfunction "2_2") (pintype "passive"))
    )
    (net (code "24") (name "Net-(R17-Pad1)") (class "Default")
      (node (ref "R17") (pin "1") (pinfunction "1_1") (pintype "passive"))
      (node (ref "R18") (pin "2") (pinfunction "2_2") (pintype "passive"))
    )
    (net (code "25") (name "Net-(R19-Pad1)") (class "Default")
      (node (ref "R19") (pin "1") (pinfunction "1_1") (pintype "passive"))
      (node (ref "R20") (pin "2") (pinfunction "2_2") (pintype "passive"))
    )
    (net (code "26") (name "Net-(R20-Pad1)") (class "Default")
      (node (ref "R20") (pin "1") (pinfunction "1_1") (pintype "passive"))
      (node (ref "R21") (pin "2") (pinfunction "2_2") (pintype "passive"))
    )
    (net (code "27") (name "Net-(R22-Pad1)") (class "Default")
      (node (ref "R22") (pin "1") (pinfunction "1_1") (pintype "passive"))
      (node (ref "R23") (pin "2") (pinfunction "2_2") (pintype "passive"))
    )
    (net (code "28") (name "Net-(R23-Pad1)") (class "Default")
      (node (ref "R23") (pin "1") (pinfunction "1_1") (pintype "passive"))
      (node (ref "R24") (pin "2") (pinfunction "2_2") (pintype "passive"))
    )
    (net (code "29") (name "Net-(R25-Pad1)") (class "Default")
      (node (ref "R25") (pin "1") (pinfunction "1_1") (pintype "passive"))
      (node (ref "R26") (pin "2") (pinfunction "2_2") (pintype "passive"))
    )
    (net (code "30") (name "Net-(R26-Pad1)") (class "Default")
      (node (ref "R26") (pin "1") (pinfunction "1_1") (pintype "passive"))
      (node (ref "R27") (pin "2") (pinfunction "2_2") (pintype "passive"))
    )
    (net (code "31") (name "Net-(R28-Pad1)") (class "Default")
      (node (ref "R28") (pin "1") (pinfunction "1_1") (pintype "passive"))
      (node (ref "R29") (pin "2") (pinfunction "2_2") (pintype "passive"))
    )
    (net (code "32") (name "Net-(R29-Pad1)") (class "Default")
      (node (ref "R29") (pin "1") (pinfunction "1_1") (pintype "passive"))
      (node (ref "R30") (pin "2") (pinfunction "2_2") (pintype "passive"))
    )
  )
)
